# lyme_shield_system_gen2.net
KiCad netlist of a schematic drawn in EAGLE
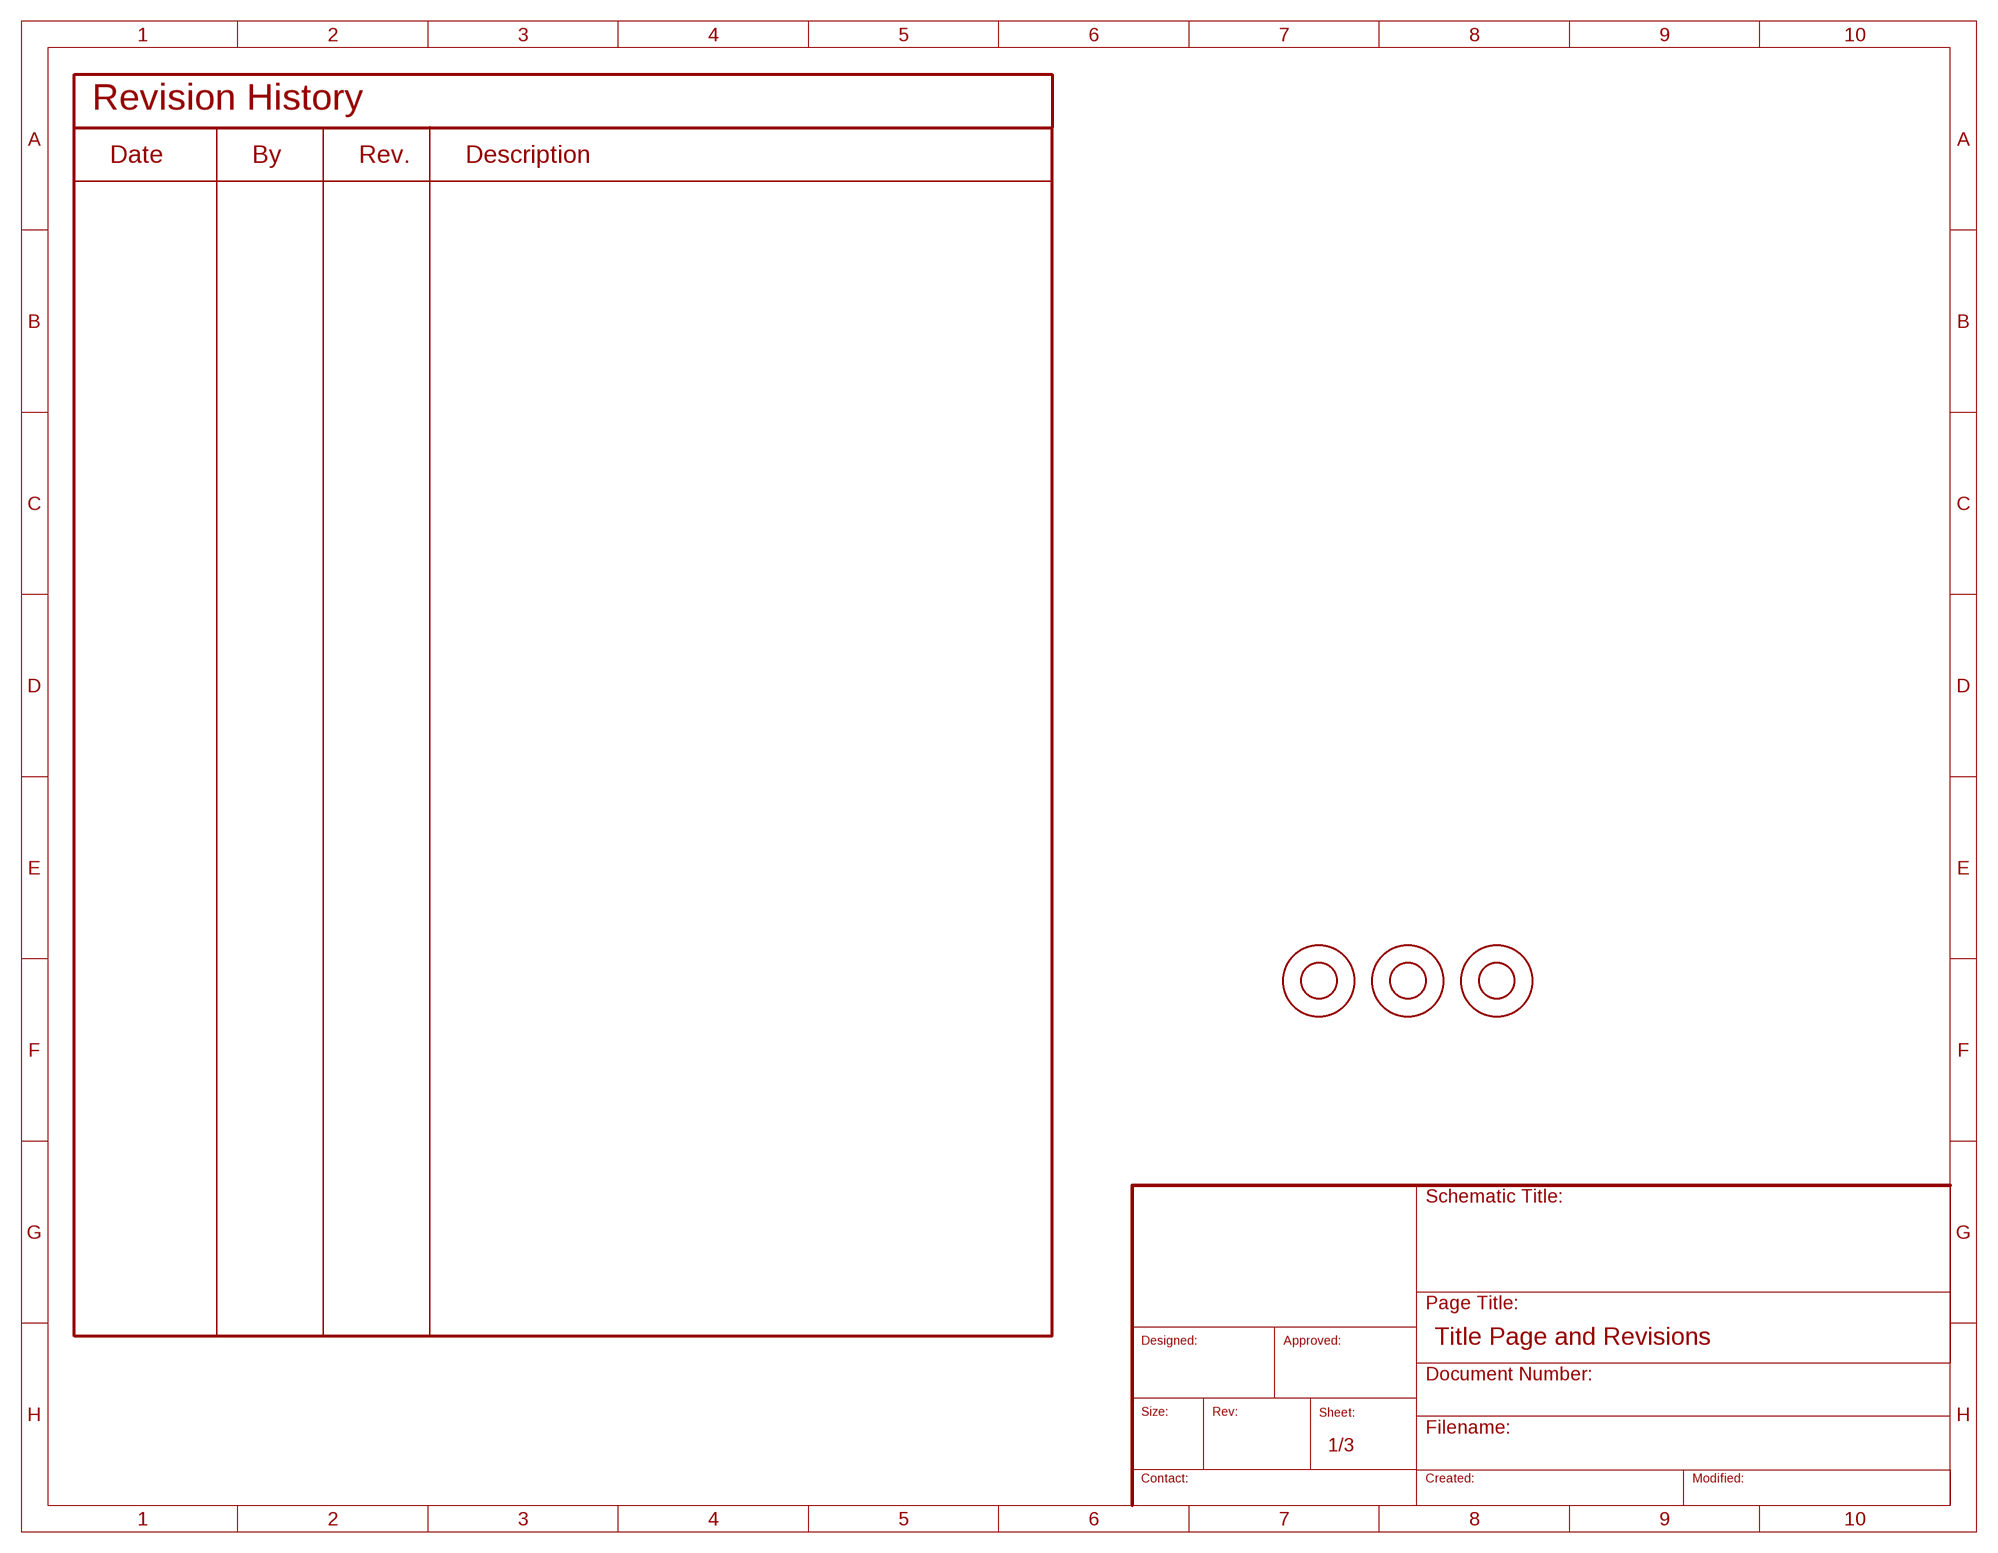
[diagram p0: schematic, sheet 1]
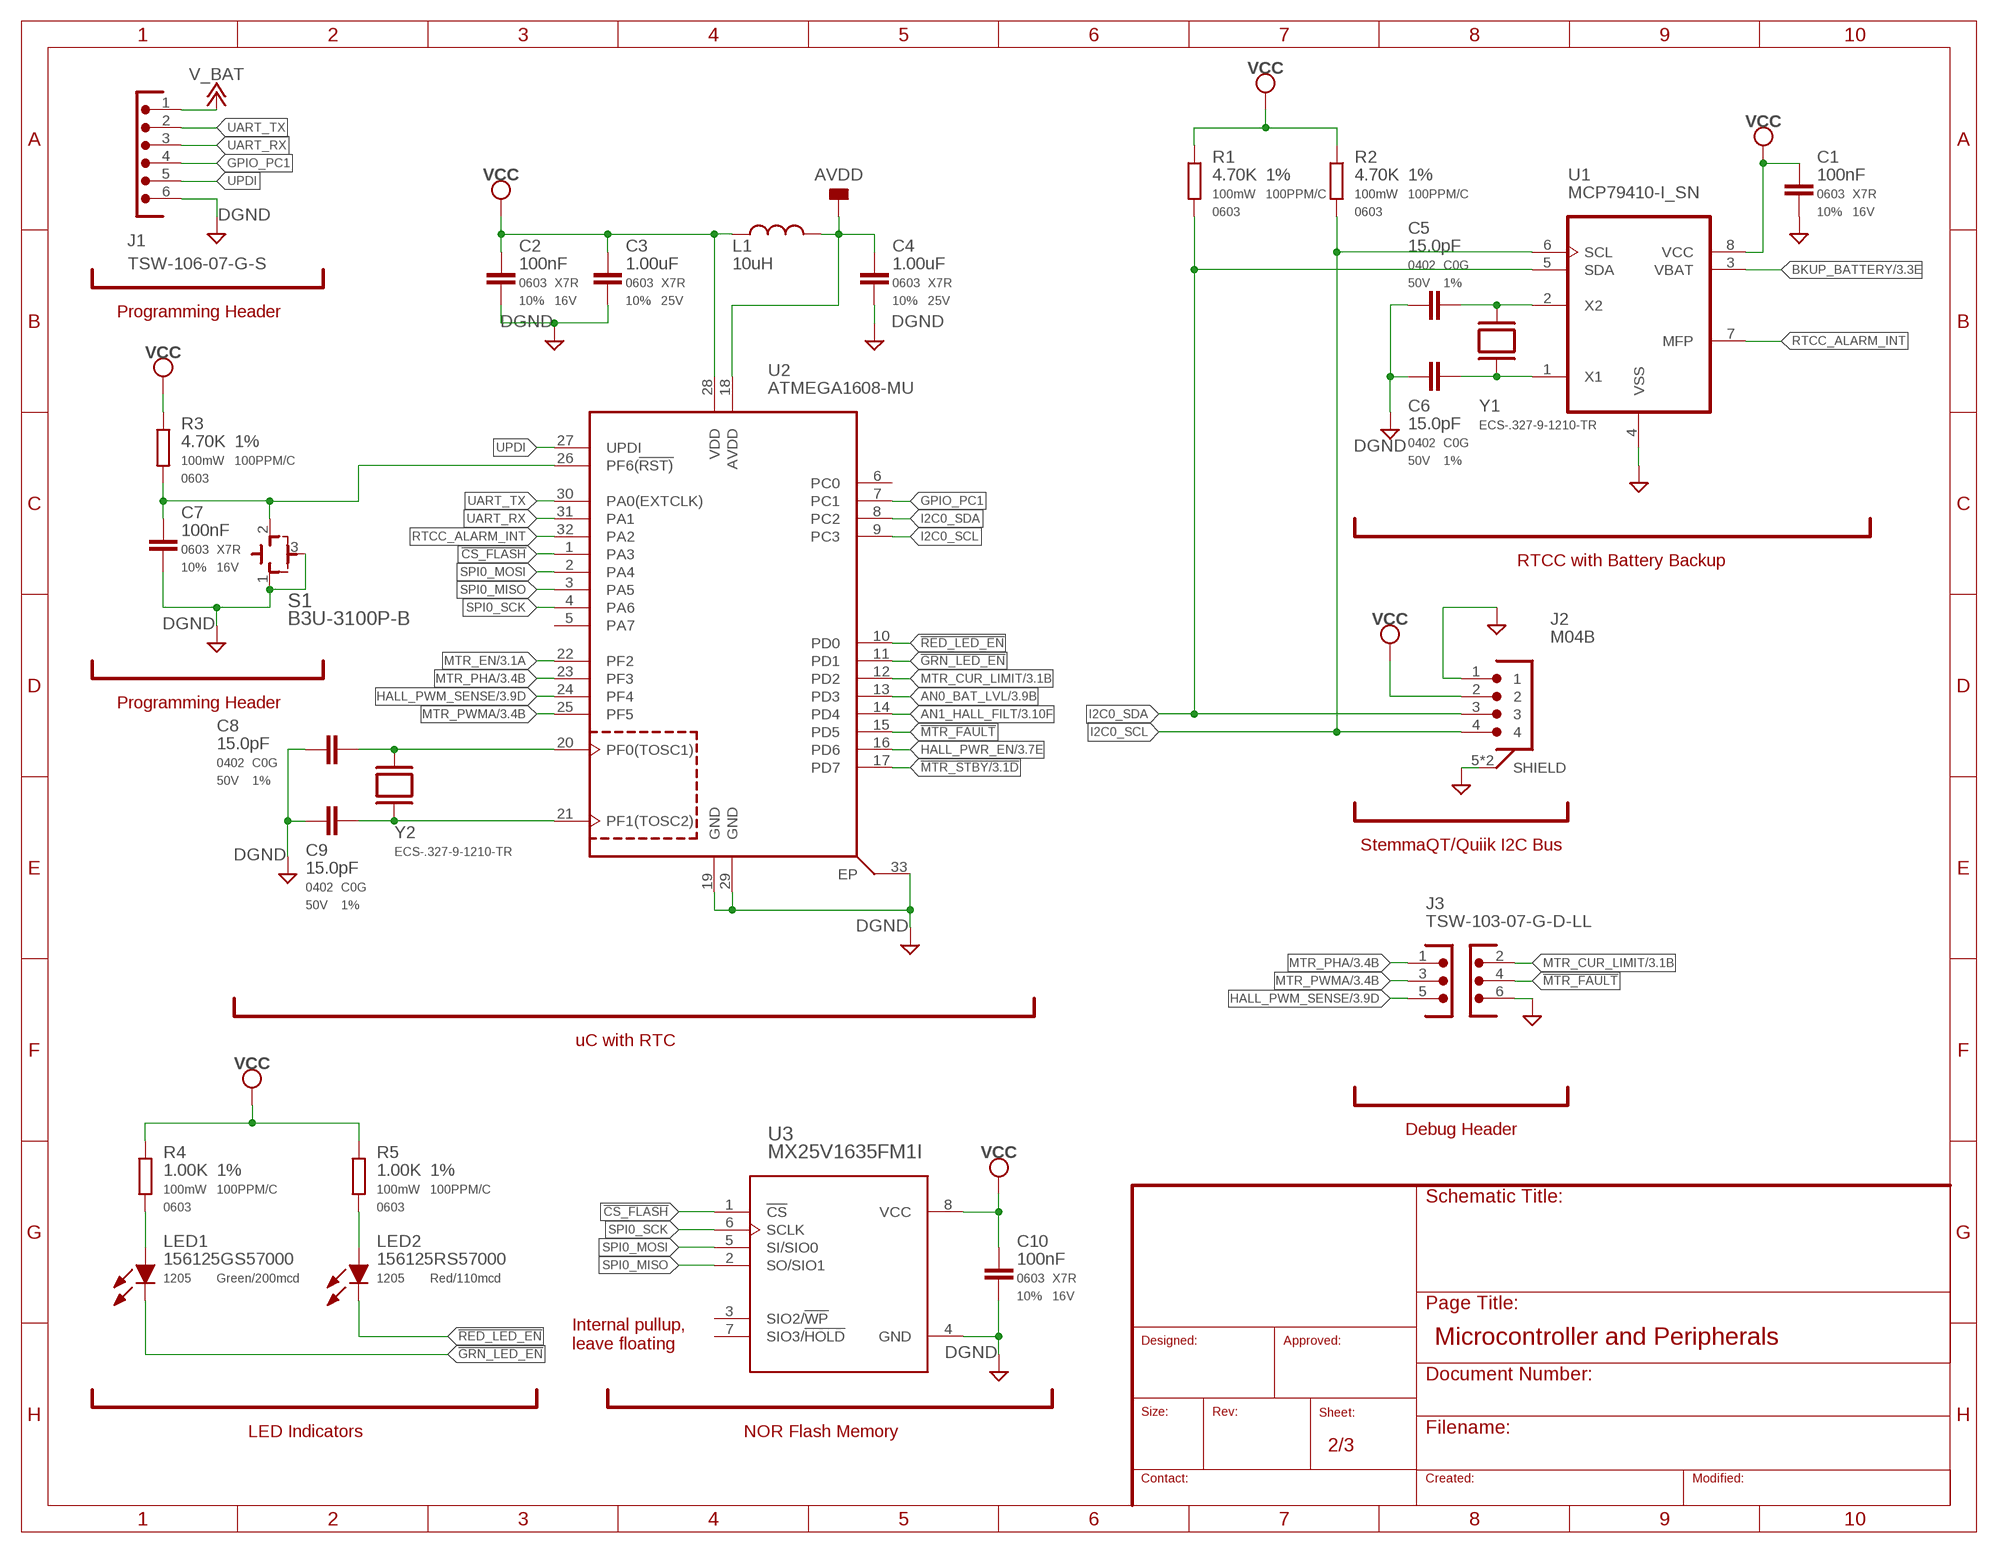
[diagram p1: schematic, sheet 2]
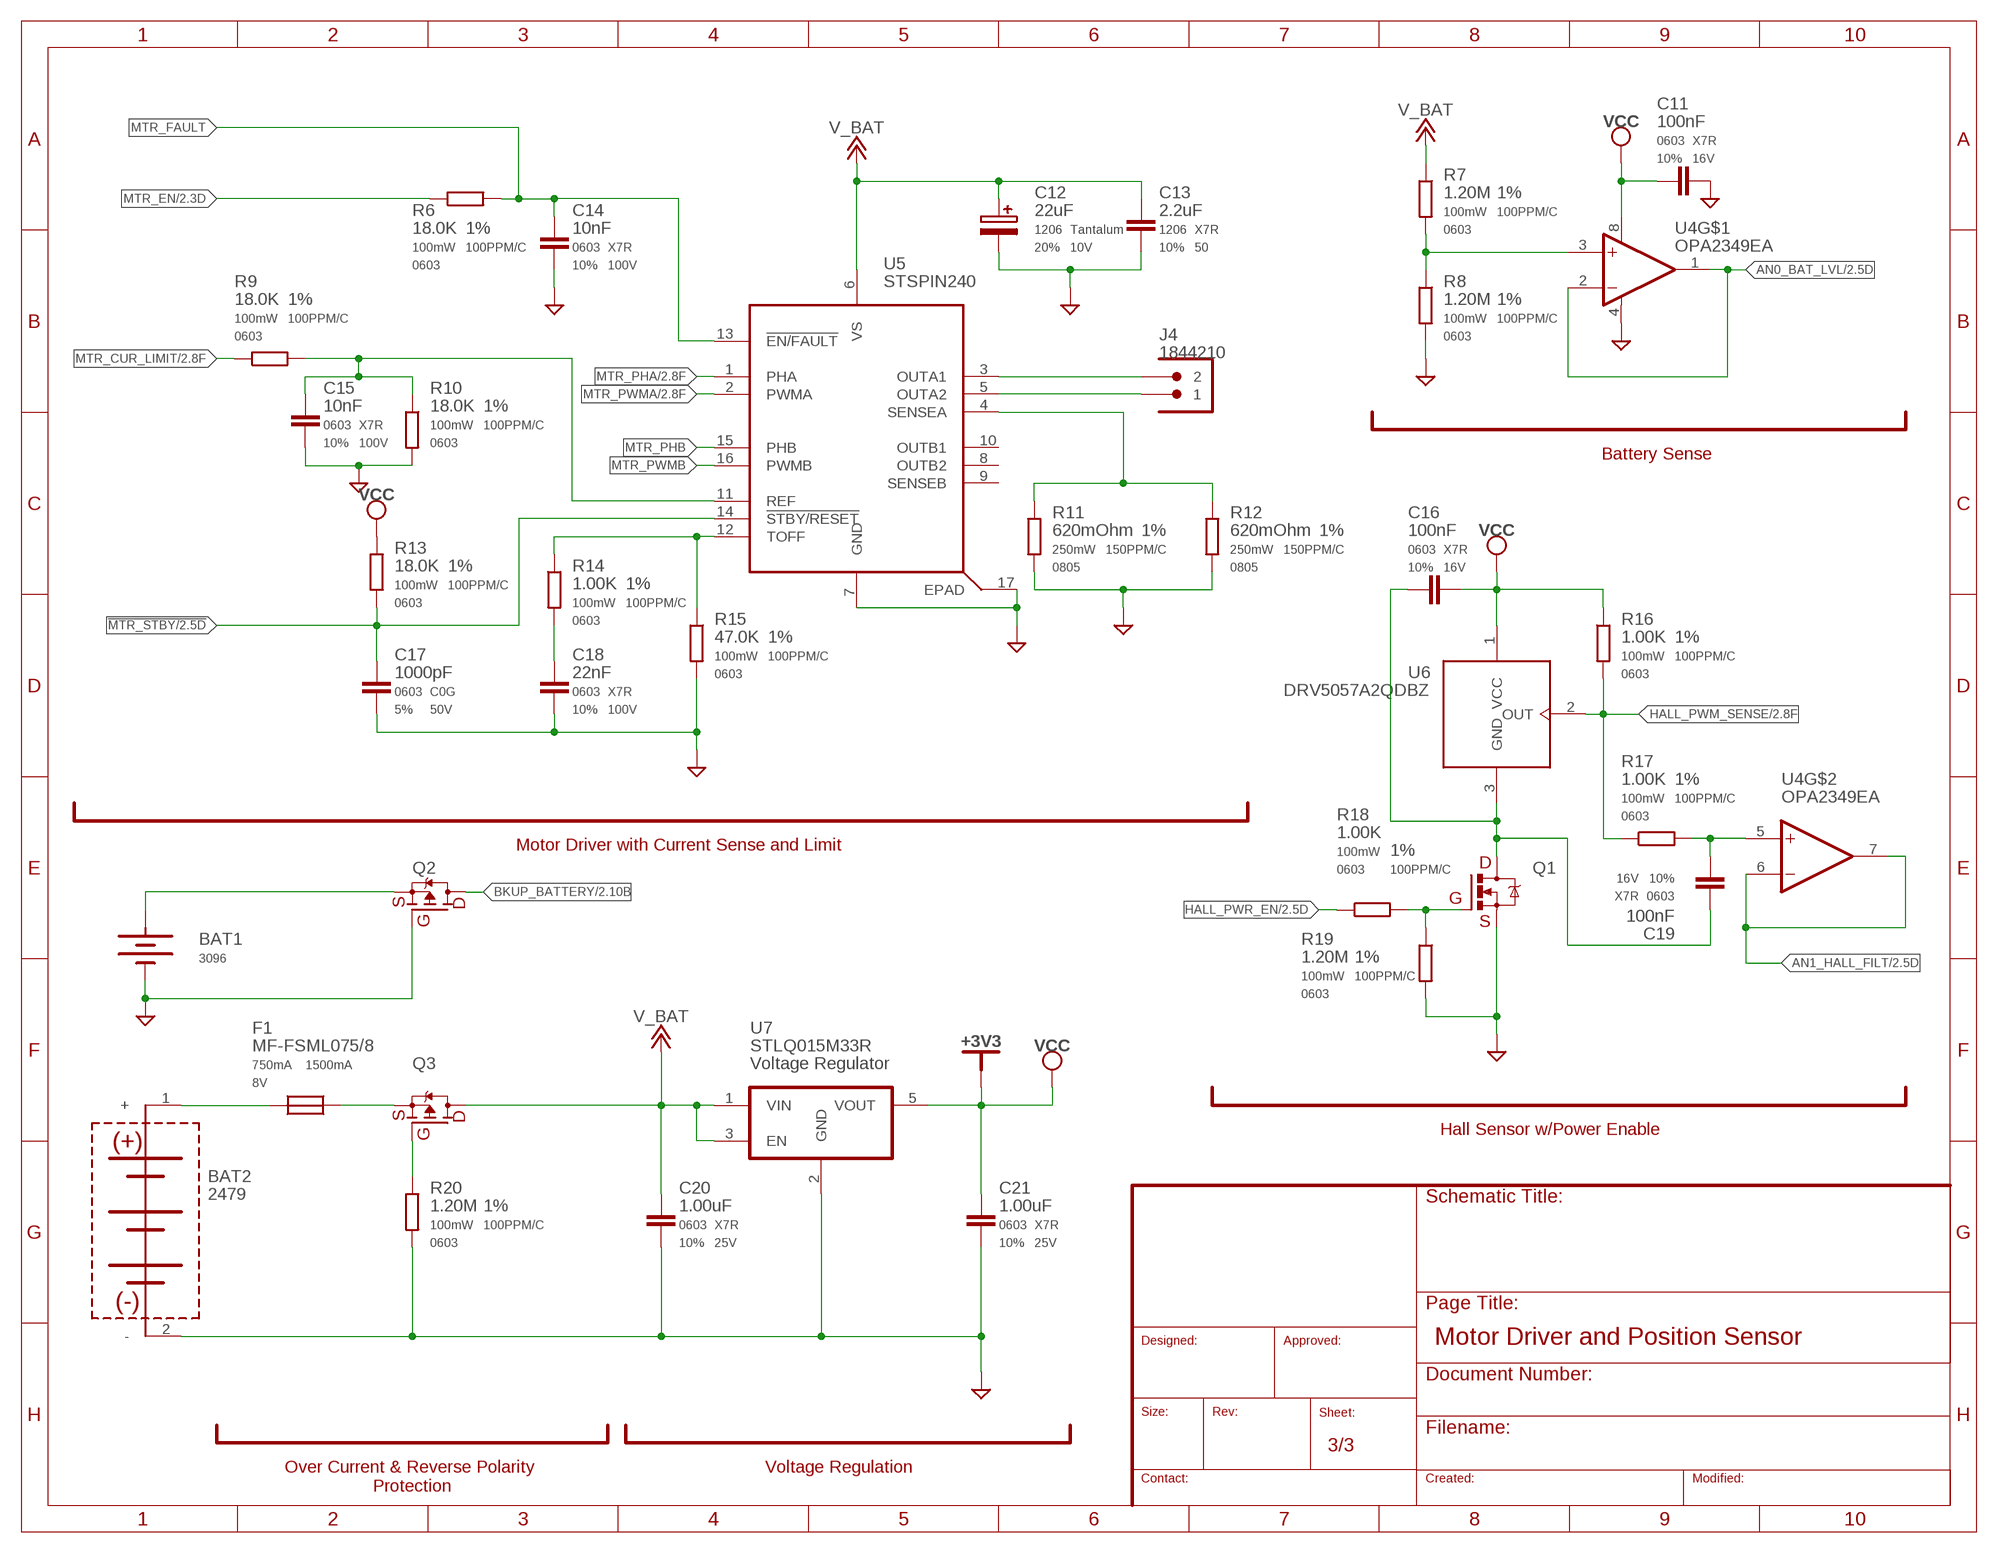
[diagram p2: schematic, sheet 3]

(export (version "E")
  (design (tool "Eeschema 10.0.6"))
  (components
    (comp (ref "BAT1")
      (value "3096")
      (footprint "eagle-import:3096")
      (fields (field (name "MOUSER_PART_NUMBER") "534-3096"))
      (libsource (lib "eagle-import") (part "3096"))
    )
    (comp (ref "BAT2")
      (value "2479")
      (footprint "eagle-import:2479")
      (fields (field (name "MOUSER_PART_NUMBER") "534-2479"))
      (libsource (lib "eagle-import") (part "2479"))
    )
    (comp (ref "C11")
      (value "100nF")
      (footprint "eagle-import:CAPC_0603_1608X90N")
      (fields
        (field (name "MANUFACTURER") "Murata")
        (field (name "PACKAGE") "0603")
        (field (name "TOL") "10%")
        (field (name "TYPE") "X7R")
        (field (name "VDC") "16V")
      )
      (libsource (lib "eagle-import") (part "GCM?188R71C104KA37J"))
    )
    (comp (ref "C12")
      (value "22uF")
      (footprint "eagle-import:CAPC_1206")
      (fields
        (field (name "MANUFACTURER") "AVX")
        (field (name "PACKAGE") "1206")
        (field (name "TOL") "20%")
        (field (name "TYPE") "Tantalum")
        (field (name "VDC") "10V")
      )
      (libsource (lib "eagle-import") (part "TAJ?C226M010RNJ"))
    )
    (comp (ref "C13")
      (value "2.2uF")
      (footprint "eagle-import:CAPC_1206")
      (fields
        (field (name "MANUFACTURER") "Murata")
        (field (name "PACKAGE") "1206")
        (field (name "TOL") "10%")
        (field (name "TYPE") "X7R")
        (field (name "VDC") "50")
      )
      (libsource (lib "eagle-import") (part "GCM?31CR71H225KA55L"))
    )
    (comp (ref "C14")
      (value "10nF")
      (footprint "eagle-import:CAPC_0603_1608X90N")
      (fields
        (field (name "MANUFACTURER") "Murata")
        (field (name "PACKAGE") "0603")
        (field (name "TOL") "10%")
        (field (name "TYPE") "X7R")
        (field (name "VDC") "100V")
      )
      (libsource (lib "eagle-import") (part "GCM?188R72A103KA37D"))
    )
    (comp (ref "C15")
      (value "10nF")
      (footprint "eagle-import:CAPC_0603_1608X90N")
      (fields
        (field (name "MANUFACTURER") "Murata")
        (field (name "PACKAGE") "0603")
        (field (name "TOL") "10%")
        (field (name "TYPE") "X7R")
        (field (name "VDC") "100V")
      )
      (libsource (lib "eagle-import") (part "GCM?188R72A103KA37D"))
    )
    (comp (ref "C16")
      (value "100nF")
      (footprint "eagle-import:CAPC_0603_1608X90N")
      (fields
        (field (name "MANUFACTURER") "Murata")
        (field (name "PACKAGE") "0603")
        (field (name "TOL") "10%")
        (field (name "TYPE") "X7R")
        (field (name "VDC") "16V")
      )
      (libsource (lib "eagle-import") (part "GCM?188R71C104KA37J"))
    )
    (comp (ref "C17")
      (value "1000pF")
      (footprint "eagle-import:CAPC_0603_1608X90N")
      (fields
        (field (name "MANUFACTURER") "Murata")
        (field (name "PACKAGE") "0603")
        (field (name "TOL") "5%")
        (field (name "TYPE") "C0G")
        (field (name "VDC") "50V")
      )
      (libsource (lib "eagle-import") (part "GCM?1885C1H102JA16J"))
    )
    (comp (ref "C18")
      (value "22nF")
      (footprint "eagle-import:CAPC_0603_1608X90N")
      (fields
        (field (name "MANUFACTURER") "Murata")
        (field (name "PACKAGE") "0603")
        (field (name "TOL") "10%")
        (field (name "TYPE") "X7R")
        (field (name "VDC") "100V")
      )
      (libsource (lib "eagle-import") (part "GCM?188R72A223KA37D"))
    )
    (comp (ref "C19")
      (value "100nF")
      (footprint "eagle-import:CAPC_0603_1608X90N")
      (fields
        (field (name "MANUFACTURER") "Murata")
        (field (name "PACKAGE") "0603")
        (field (name "TOL") "10%")
        (field (name "TYPE") "X7R")
        (field (name "VDC") "16V")
      )
      (libsource (lib "eagle-import") (part "GCM?188R71C104KA37J"))
    )
    (comp (ref "C20")
      (value "1.00uF")
      (footprint "eagle-import:CAPC_0603_1608X90N")
      (fields
        (field (name "MANUFACTURER") "Murata")
        (field (name "PACKAGE") "0603")
        (field (name "TOL") "10%")
        (field (name "TYPE") "X7R")
        (field (name "VDC") "25V")
      )
      (libsource (lib "eagle-import") (part "GCM?188R71E105KA64D"))
    )
    (comp (ref "C21")
      (value "1.00uF")
      (footprint "eagle-import:CAPC_0603_1608X90N")
      (fields
        (field (name "MANUFACTURER") "Murata")
        (field (name "PACKAGE") "0603")
        (field (name "TOL") "10%")
        (field (name "TYPE") "X7R")
        (field (name "VDC") "25V")
      )
      (libsource (lib "eagle-import") (part "GCM?188R71E105KA64D"))
    )
    (comp (ref "F1")
      (value "MF-FSML075/8")
      (footprint "eagle-import:FUSC1608X70N")
      (fields (field (name "IHOLD") "750mA") (field (name "ITRIP") "1500mA") (field (name "VMAX") "8V"))
      (libsource (lib "eagle-import") (part "MF-FSML?075/8"))
    )
    (comp (ref "J4")
      (value "1844210")
      (footprint "eagle-import:1844210-2-3.50")
      (libsource (lib "eagle-import") (part "1844210"))
    )
    (comp (ref "Q1")
      (value "FDN5632N-F085-FDN5632N_F085")
      (footprint "eagle-import:SOT-23")
      (fields (field (name "MANUFACTURER") "ON Semiconductor"))
      (libsource (lib "eagle-import") (part "FDN5632N-F085-FDN5632N_F085"))
    )
    (comp (ref "Q2")
      (value "PMOS_DMP2035U-7")
      (footprint "eagle-import:SOT-23")
      (fields (field (name "MF") "Diodes Incorporated") (field (name "MP") "DMP2035U-7"))
      (libsource (lib "eagle-import") (part "PMOS_DMP2035U-7"))
    )
    (comp (ref "Q3")
      (value "PMOS_DMP2035U-7")
      (footprint "eagle-import:SOT-23")
      (fields (field (name "MF") "Diodes Incorporated") (field (name "MP") "DMP2035U-7"))
      (libsource (lib "eagle-import") (part "PMOS_DMP2035U-7"))
    )
    (comp (ref "R6")
      (value "18.0K")
      (footprint "eagle-import:R0603K")
      (fields
        (field (name "MF") "Vishay")
        (field (name "PACKAGE") "0603")
        (field (name "PWR_RATE") "100mW")
        (field (name "TEMPCO") "100PPM/C")
        (field (name "TOLERANCE") "1%")
      )
      (libsource (lib "eagle-import") (part "CRCW?060318K0FKEAC"))
    )
    (comp (ref "R7")
      (value "1.20M")
      (footprint "eagle-import:R0603K")
      (fields
        (field (name "MF") "Vishay")
        (field (name "PACKAGE") "0603")
        (field (name "PWR_RATE") "100mW")
        (field (name "TEMPCO") "100PPM/C")
        (field (name "TOLERANCE") "1%")
      )
      (libsource (lib "eagle-import") (part "CRCW?06031M20FKEA"))
    )
    (comp (ref "R8")
      (value "1.20M")
      (footprint "eagle-import:R0603K")
      (fields
        (field (name "MF") "Vishay")
        (field (name "PACKAGE") "0603")
        (field (name "PWR_RATE") "100mW")
        (field (name "TEMPCO") "100PPM/C")
        (field (name "TOLERANCE") "1%")
      )
      (libsource (lib "eagle-import") (part "CRCW?06031M20FKEA"))
    )
    (comp (ref "R9")
      (value "18.0K")
      (footprint "eagle-import:R0603K")
      (fields
        (field (name "MF") "Vishay")
        (field (name "PACKAGE") "0603")
        (field (name "PWR_RATE") "100mW")
        (field (name "TEMPCO") "100PPM/C")
        (field (name "TOLERANCE") "1%")
      )
      (libsource (lib "eagle-import") (part "CRCW?060318K0FKEAC"))
    )
    (comp (ref "R10")
      (value "18.0K")
      (footprint "eagle-import:R0603K")
      (fields
        (field (name "MF") "Vishay")
        (field (name "PACKAGE") "0603")
        (field (name "PWR_RATE") "100mW")
        (field (name "TEMPCO") "100PPM/C")
        (field (name "TOLERANCE") "1%")
      )
      (libsource (lib "eagle-import") (part "CRCW?060318K0FKEAC"))
    )
    (comp (ref "R11")
      (value "620mOhm")
      (footprint "eagle-import:R0805K")
      (fields
        (field (name "MANUFACTURER") "Panasonic")
        (field (name "PACKAGE") "0805")
        (field (name "PWR_RATE") "250mW")
        (field (name "TEMPCO") "150PPM/C")
        (field (name "TOLERANCE") "1%")
      )
      (libsource (lib "eagle-import") (part "ERJ?U6QFR62V"))
    )
    (comp (ref "R12")
      (value "620mOhm")
      (footprint "eagle-import:R0805K")
      (fields
        (field (name "MANUFACTURER") "Panasonic")
        (field (name "PACKAGE") "0805")
        (field (name "PWR_RATE") "250mW")
        (field (name "TEMPCO") "150PPM/C")
        (field (name "TOLERANCE") "1%")
      )
      (libsource (lib "eagle-import") (part "ERJ?U6QFR62V"))
    )
    (comp (ref "R13")
      (value "18.0K")
      (footprint "eagle-import:R0603K")
      (fields
        (field (name "MF") "Vishay")
        (field (name "PACKAGE") "0603")
        (field (name "PWR_RATE") "100mW")
        (field (name "TEMPCO") "100PPM/C")
        (field (name "TOLERANCE") "1%")
      )
      (libsource (lib "eagle-import") (part "CRCW?060318K0FKEAC"))
    )
    (comp (ref "R14")
      (value "1.00K")
      (footprint "eagle-import:R0603K")
      (fields
        (field (name "MF") "Vishay")
        (field (name "PACKAGE") "0603")
        (field (name "PWR_RATE") "100mW")
        (field (name "TEMPCO") "100PPM/C")
        (field (name "TOLERANCE") "1%")
      )
      (libsource (lib "eagle-import") (part "CRCW?06031K00FKEAC"))
    )
    (comp (ref "R15")
      (value "47.0K")
      (footprint "eagle-import:R0603K")
      (fields
        (field (name "MF") "Vishay")
        (field (name "PACKAGE") "0603")
        (field (name "PWR_RATE") "100mW")
        (field (name "TEMPCO") "100PPM/C")
        (field (name "TOLERANCE") "1%")
      )
      (libsource (lib "eagle-import") (part "CRCW?060347K0FKEAC"))
    )
    (comp (ref "R16")
      (value "1.00K")
      (footprint "eagle-import:R0603K")
      (fields
        (field (name "MF") "Vishay")
        (field (name "PACKAGE") "0603")
        (field (name "PWR_RATE") "100mW")
        (field (name "TEMPCO") "100PPM/C")
        (field (name "TOLERANCE") "1%")
      )
      (libsource (lib "eagle-import") (part "CRCW?06031K00FKEAC"))
    )
    (comp (ref "R17")
      (value "1.00K")
      (footprint "eagle-import:R0603K")
      (fields
        (field (name "MF") "Vishay")
        (field (name "PACKAGE") "0603")
        (field (name "PWR_RATE") "100mW")
        (field (name "TEMPCO") "100PPM/C")
        (field (name "TOLERANCE") "1%")
      )
      (libsource (lib "eagle-import") (part "CRCW?06031K00FKEAC"))
    )
    (comp (ref "R18")
      (value "1.00K")
      (footprint "eagle-import:R0603K")
      (fields
        (field (name "MF") "Vishay")
        (field (name "PACKAGE") "0603")
        (field (name "PWR_RATE") "100mW")
        (field (name "TEMPCO") "100PPM/C")
        (field (name "TOLERANCE") "1%")
      )
      (libsource (lib "eagle-import") (part "CRCW?06031K00FKEAC"))
    )
    (comp (ref "R19")
      (value "1.20M")
      (footprint "eagle-import:R0603K")
      (fields
        (field (name "MF") "Vishay")
        (field (name "PACKAGE") "0603")
        (field (name "PWR_RATE") "100mW")
        (field (name "TEMPCO") "100PPM/C")
        (field (name "TOLERANCE") "1%")
      )
      (libsource (lib "eagle-import") (part "CRCW?06031M20FKEA"))
    )
    (comp (ref "R20")
      (value "1.20M")
      (footprint "eagle-import:R0603K")
      (fields
        (field (name "MF") "Vishay")
        (field (name "PACKAGE") "0603")
        (field (name "PWR_RATE") "100mW")
        (field (name "TEMPCO") "100PPM/C")
        (field (name "TOLERANCE") "1%")
      )
      (libsource (lib "eagle-import") (part "CRCW?06031M20FKEA"))
    )
    (comp (ref "U4")
      (value "OPA2349EA")
      (footprint "eagle-import:SOT65P280X145-8N")
      (fields
        (field (name "ARROW_PART_NUMBER") "OPA2349EA/3K")
        (field (name "MOUSER_PART_NUMBER") "595-OPA2349EA/3K")
      )
      (libsource (lib "eagle-import") (part "OPA2349EA"))
    )
    (comp (ref "U5")
      (value "STSPIN240")
      (footprint "eagle-import:VFQFPN(3X3X1.0MM-16L)")
      (fields (field (name "MOUSER_PART_NUMBER") "511-STSPIN240"))
      (libsource (lib "eagle-import") (part "STSPIN240"))
    )
    (comp (ref "U6")
      (value "DRV5057A2QDBZ")
      (footprint "eagle-import:SOT95P237X112-3N")
      (libsource (lib "eagle-import") (part "DRV5057QDBZA2"))
    )
    (comp (ref "U7")
      (value "STLQ015M33R")
      (footprint "eagle-import:SOT23-5L")
      (fields
        (field (name "DESC") "Voltage Regulator")
        (field (name "MF") "STM")
        (field (name "VOLTAGE") "3.3V")
      )
      (libsource (lib "eagle-import") (part "STLQ015MR33"))
    )
    (comp (ref "C1")
      (value "100nF")
      (footprint "eagle-import:CAPC_0603_1608X90N")
      (fields
        (field (name "MANUFACTURER") "Murata")
        (field (name "PACKAGE") "0603")
        (field (name "TOL") "10%")
        (field (name "TYPE") "X7R")
        (field (name "VDC") "16V")
      )
      (libsource (lib "eagle-import") (part "GCM?188R71C104KA37J"))
    )
    (comp (ref "C2")
      (value "100nF")
      (footprint "eagle-import:CAPC_0603_1608X90N")
      (fields
        (field (name "MANUFACTURER") "Murata")
        (field (name "PACKAGE") "0603")
        (field (name "TOL") "10%")
        (field (name "TYPE") "X7R")
        (field (name "VDC") "16V")
      )
      (libsource (lib "eagle-import") (part "GCM?188R71C104KA37J"))
    )
    (comp (ref "C3")
      (value "1.00uF")
      (footprint "eagle-import:CAPC_0603_1608X90N")
      (fields
        (field (name "MANUFACTURER") "Murata")
        (field (name "PACKAGE") "0603")
        (field (name "TOL") "10%")
        (field (name "TYPE") "X7R")
        (field (name "VDC") "25V")
      )
      (libsource (lib "eagle-import") (part "GCM?188R71E105KA64D"))
    )
    (comp (ref "C4")
      (value "1.00uF")
      (footprint "eagle-import:CAPC_0603_1608X90N")
      (fields
        (field (name "MANUFACTURER") "Murata")
        (field (name "PACKAGE") "0603")
        (field (name "TOL") "10%")
        (field (name "TYPE") "X7R")
        (field (name "VDC") "25V")
      )
      (libsource (lib "eagle-import") (part "GCM?188R71E105KA64D"))
    )
    (comp (ref "C5")
      (value "15.0pF")
      (footprint "eagle-import:CAPC_0402_1005X55N")
      (fields
        (field (name "MANUFACTURER") "Murata")
        (field (name "PACKAGE") "0402")
        (field (name "TOL") "1%")
        (field (name "TYPE") "C0G")
        (field (name "VDC") "50V")
      )
      (libsource (lib "eagle-import") (part "GCM?1555C1H150FA16D"))
    )
    (comp (ref "C6")
      (value "15.0pF")
      (footprint "eagle-import:CAPC_0402_1005X55N")
      (fields
        (field (name "MANUFACTURER") "Murata")
        (field (name "PACKAGE") "0402")
        (field (name "TOL") "1%")
        (field (name "TYPE") "C0G")
        (field (name "VDC") "50V")
      )
      (libsource (lib "eagle-import") (part "GCM?1555C1H150FA16D"))
    )
    (comp (ref "C7")
      (value "100nF")
      (footprint "eagle-import:CAPC_0603_1608X90N")
      (fields
        (field (name "MANUFACTURER") "Murata")
        (field (name "PACKAGE") "0603")
        (field (name "TOL") "10%")
        (field (name "TYPE") "X7R")
        (field (name "VDC") "16V")
      )
      (libsource (lib "eagle-import") (part "GCM?188R71C104KA37J"))
    )
    (comp (ref "C8")
      (value "15.0pF")
      (footprint "eagle-import:CAPC_0402_1005X55N")
      (fields
        (field (name "MANUFACTURER") "Murata")
        (field (name "PACKAGE") "0402")
        (field (name "TOL") "1%")
        (field (name "TYPE") "C0G")
        (field (name "VDC") "50V")
      )
      (libsource (lib "eagle-import") (part "GCM?1555C1H150FA16D"))
    )
    (comp (ref "C9")
      (value "15.0pF")
      (footprint "eagle-import:CAPC_0402_1005X55N")
      (fields
        (field (name "MANUFACTURER") "Murata")
        (field (name "PACKAGE") "0402")
        (field (name "TOL") "1%")
        (field (name "TYPE") "C0G")
        (field (name "VDC") "50V")
      )
      (libsource (lib "eagle-import") (part "GCM?1555C1H150FA16D"))
    )
    (comp (ref "C10")
      (value "100nF")
      (footprint "eagle-import:CAPC_0603_1608X90N")
      (fields
        (field (name "MANUFACTURER") "Murata")
        (field (name "PACKAGE") "0603")
        (field (name "TOL") "10%")
        (field (name "TYPE") "X7R")
        (field (name "VDC") "16V")
      )
      (libsource (lib "eagle-import") (part "GCM?188R71C104KA37J"))
    )
    (comp (ref "J1")
      (value "TSW-106-07-G-S")
      (footprint "eagle-import:HDR-100MIL-1X6-THRU")
      (libsource (lib "eagle-import") (part "TSW-106-07-G-S"))
    )
    (comp (ref "J2")
      (value "M04B")
      (footprint "eagle-import:SM04B-SRSS-TB(LFSN)")
      (fields (field (name "MANUFACTURER_PART_NUMBER") "SM04B-SRSS-TB(LFSN)"))
      (libsource (lib "eagle-import") (part "?M04B"))
    )
    (comp (ref "J3")
      (value "TSW-103-07-G-D-LL")
      (footprint "eagle-import:HDRV6W64P254_2X3_762X495X838P")
      (fields (field (name "MOUSER_PART_NUMBER") "200-TSW10307GDLL"))
      (libsource (lib "eagle-import") (part "TSW-103-07-G-D-LL"))
    )
    (comp (ref "L1")
      (value "10uH")
      (footprint "eagle-import:INDC1608X90N")
      (fields (field (name "MF") "Taiyo Yuden") (field (name "MP") "LB1608T100M"))
      (libsource (lib "eagle-import") (part "LB1608T100M"))
    )
    (comp (ref "LED1")
      (value "156125GS57000")
      (footprint "eagle-import:LEDC3212X120N")
      (fields (field (name "PACKAGE") "1205"))
      (libsource (lib "eagle-import") (part "15612557000GS"))
    )
    (comp (ref "LED2")
      (value "156125RS57000")
      (footprint "eagle-import:LEDC3212X120N")
      (fields (field (name "PACKAGE") "1205"))
      (libsource (lib "eagle-import") (part "15612557000RS"))
    )
    (comp (ref "R1")
      (value "4.70K")
      (footprint "eagle-import:R0603K")
      (fields
        (field (name "MF") "Vishay")
        (field (name "PACKAGE") "0603")
        (field (name "PWR_RATE") "100mW")
        (field (name "TEMPCO") "100PPM/C")
        (field (name "TOLERANCE") "1%")
      )
      (libsource (lib "eagle-import") (part "CRCW?06034K70FKEA"))
    )
    (comp (ref "R2")
      (value "4.70K")
      (footprint "eagle-import:R0603K")
      (fields
        (field (name "MF") "Vishay")
        (field (name "PACKAGE") "0603")
        (field (name "PWR_RATE") "100mW")
        (field (name "TEMPCO") "100PPM/C")
        (field (name "TOLERANCE") "1%")
      )
      (libsource (lib "eagle-import") (part "CRCW?06034K70FKEA"))
    )
    (comp (ref "R3")
      (value "4.70K")
      (footprint "eagle-import:R0603K")
      (fields
        (field (name "MF") "Vishay")
        (field (name "PACKAGE") "0603")
        (field (name "PWR_RATE") "100mW")
        (field (name "TEMPCO") "100PPM/C")
        (field (name "TOLERANCE") "1%")
      )
      (libsource (lib "eagle-import") (part "CRCW?06034K70FKEA"))
    )
    (comp (ref "R4")
      (value "1.00K")
      (footprint "eagle-import:R0603K")
      (fields
        (field (name "MF") "Vishay")
        (field (name "PACKAGE") "0603")
        (field (name "PWR_RATE") "100mW")
        (field (name "TEMPCO") "100PPM/C")
        (field (name "TOLERANCE") "1%")
      )
      (libsource (lib "eagle-import") (part "CRCW?06031K00FKEAC"))
    )
    (comp (ref "R5")
      (value "1.00K")
      (footprint "eagle-import:R0603K")
      (fields
        (field (name "MF") "Vishay")
        (field (name "PACKAGE") "0603")
        (field (name "PWR_RATE") "100mW")
        (field (name "TEMPCO") "100PPM/C")
        (field (name "TOLERANCE") "1%")
      )
      (libsource (lib "eagle-import") (part "CRCW?06031K00FKEAC"))
    )
    (comp (ref "S1")
      (value "B3U-3100P-B")
      (footprint "eagle-import:B3U-3100P-B")
      (libsource (lib "eagle-import") (part "B3U-3100P-B"))
    )
    (comp (ref "U1")
      (value "MCP79410-I_SN")
      (footprint "eagle-import:SOIC127P600X175-8N")
      (fields
        (field (name "ARROW_PART_NUMBER") "MCP79410-I/SN")
        (field (name "MOUSER_PART_NUMBER") "579-MCP79410-I/SN")
      )
      (libsource (lib "eagle-import") (part "MCP79410-I_SN"))
    )
    (comp (ref "U2")
      (value "ATMEGA1608-MU")
      (footprint "eagle-import:QFN50P500X500X90-33N")
      (fields (field (name "MOUSER_PART_NUMBER") "556-ATMEGA1608-MU"))
      (libsource (lib "eagle-import") (part "ATMEGA1608-MU"))
    )
    (comp (ref "U3")
      (value "MX25V1635FM1I")
      (footprint "eagle-import:SOIC127P600X175-8N")
      (fields (field (name "MANUFACTURER") "Macronix"))
      (libsource (lib "eagle-import") (part "MX25V?M1I1635F"))
    )
    (comp (ref "Y1")
      (value "ECS-.327-9-1210-TR")
      (footprint "eagle-import:XTAL_ECS-.327-9-1210-TR")
      (fields (field (name "DIGI-KEY_PART_NUMBER") "XC2283CT-ND") (field (name "MF") "ECS Inc."))
      (libsource (lib "eagle-import") (part "ECS-.327-9-1210-TR"))
    )
    (comp (ref "Y2")
      (value "ECS-.327-9-1210-TR")
      (footprint "eagle-import:XTAL_ECS-.327-9-1210-TR")
      (fields (field (name "DIGI-KEY_PART_NUMBER") "XC2283CT-ND") (field (name "MF") "ECS Inc."))
      (libsource (lib "eagle-import") (part "ECS-.327-9-1210-TR"))
    )
    (comp (ref "FID1")
      (value "FIDUCIAL_1MM_TOP_BOTTOM")
      (footprint "eagle-import:FIDUCIAL_1MM_TOP_BOTTOM")
      (libsource (lib "eagle-import") (part "FIDUCIAL_1MM_TOP_BOTTOM"))
    )
    (comp (ref "FID2")
      (value "FIDUCIAL_1MM_TOP_BOTTOM")
      (footprint "eagle-import:FIDUCIAL_1MM_TOP_BOTTOM")
      (libsource (lib "eagle-import") (part "FIDUCIAL_1MM_TOP_BOTTOM"))
    )
    (comp (ref "FID3")
      (value "FIDUCIAL_1MM_TOP_BOTTOM")
      (footprint "eagle-import:FIDUCIAL_1MM_TOP_BOTTOM")
      (libsource (lib "eagle-import") (part "FIDUCIAL_1MM_TOP_BOTTOM"))
    )
  )
  (nets
    (net (code "1") (name "+3V3") (class "Default")
      (node (ref "C1") (pin "1") (pinfunction "1_1") (pintype "passive"))
      (node (ref "C10") (pin "1") (pinfunction "1_1") (pintype "passive"))
      (node (ref "C11") (pin "2") (pinfunction "2_2") (pintype "passive"))
      (node (ref "C16") (pin "1") (pinfunction "1_1") (pintype "passive"))
      (node (ref "C2") (pin "1") (pinfunction "1_1") (pintype "passive"))
      (node (ref "C21") (pin "1") (pinfunction "1_1") (pintype "passive"))
      (node (ref "C3") (pin "1") (pinfunction "1_1") (pintype "passive"))
      (node (ref "J2") (pin "2") (pinfunction "2_2") (pintype "bidirectional"))
      (node (ref "L1") (pin "1") (pinfunction "1_1") (pintype "passive"))
      (node (ref "R1") (pin "1") (pinfunction "1_1") (pintype "passive"))
      (node (ref "R13") (pin "1") (pinfunction "1_1") (pintype "passive"))
      (node (ref "R16") (pin "1") (pinfunction "1_1") (pintype "passive"))
      (node (ref "R2") (pin "1") (pinfunction "1_1") (pintype "passive"))
      (node (ref "R3") (pin "1") (pinfunction "1_1") (pintype "passive"))
      (node (ref "R4") (pin "1") (pinfunction "1_1") (pintype "passive"))
      (node (ref "R5") (pin "1") (pinfunction "1_1") (pintype "passive"))
      (node (ref "U1") (pin "8") (pinfunction "VCC_8") (pintype "bidirectional"))
      (node (ref "U2") (pin "28") (pinfunction "VDD_28") (pintype "bidirectional"))
      (node (ref "U3") (pin "8") (pinfunction "VCC_8") (pintype "power_in"))
      (node (ref "U4") (pin "8") (pinfunction "V+_8") (pintype "power_in"))
      (node (ref "U6") (pin "1") (pinfunction "VCC_1") (pintype "bidirectional"))
      (node (ref "U7") (pin "5") (pinfunction "VOUT_5") (pintype "power_in"))
    )
    (net (code "2") (name "AN0_BAT_LVL") (class "Default")
      (node (ref "U2") (pin "13") (pinfunction "PD3_13") (pintype "bidirectional"))
      (node (ref "U4") (pin "1") (pinfunction "OUT_1") (pintype "output"))
      (node (ref "U4") (pin "2") (pinfunction "-IN_2") (pintype "input"))
    )
    (net (code "3") (name "AN1_HALL_FILT") (class "Default")
      (node (ref "U2") (pin "14") (pinfunction "PD4_14") (pintype "bidirectional"))
      (node (ref "U4") (pin "6") (pinfunction "-IN_6") (pintype "input"))
      (node (ref "U4") (pin "7") (pinfunction "OUT_7") (pintype "output"))
    )
    (net (code "4") (name "AVDD") (class "Default")
      (node (ref "C4") (pin "1") (pinfunction "1_1") (pintype "passive"))
      (node (ref "L1") (pin "2") (pinfunction "2_2") (pintype "passive"))
      (node (ref "U2") (pin "18") (pinfunction "AVDD_18") (pintype "bidirectional"))
    )
    (net (code "5") (name "BKUP_BATTERY") (class "Default")
      (node (ref "Q2") (pin "1") (pinfunction "D_1") (pintype "passive"))
      (node (ref "U1") (pin "3") (pinfunction "VBAT_3") (pintype "bidirectional"))
    )
    (net (code "6") (name "DGND") (class "Default")
      (node (ref "BAT1") (pin "1") (pinfunction "-_1") (pintype "power_in"))
      (node (ref "BAT1") (pin "3") (pinfunction "-_3") (pintype "power_in"))
      (node (ref "BAT2") (pin "2") (pinfunction "-_2") (pintype "bidirectional"))
      (node (ref "C1") (pin "2") (pinfunction "2_2") (pintype "passive"))
      (node (ref "C10") (pin "2") (pinfunction "2_2") (pintype "passive"))
      (node (ref "C11") (pin "1") (pinfunction "1_1") (pintype "passive"))
      (node (ref "C12") (pin "2") (pinfunction "-_2") (pintype "bidirectional"))
      (node (ref "C13") (pin "2") (pinfunction "2_2") (pintype "passive"))
      (node (ref "C14") (pin "2") (pinfunction "2_2") (pintype "passive"))
      (node (ref "C15") (pin "2") (pinfunction "2_2") (pintype "passive"))
      (node (ref "C17") (pin "2") (pinfunction "2_2") (pintype "passive"))
      (node (ref "C18") (pin "2") (pinfunction "2_2") (pintype "passive"))
      (node (ref "C2") (pin "2") (pinfunction "2_2") (pintype "passive"))
      (node (ref "C20") (pin "2") (pinfunction "2_2") (pintype "passive"))
      (node (ref "C21") (pin "2") (pinfunction "2_2") (pintype "passive"))
      (node (ref "C3") (pin "2") (pinfunction "2_2") (pintype "passive"))
      (node (ref "C4") (pin "2") (pinfunction "2_2") (pintype "passive"))
      (node (ref "C5") (pin "2") (pinfunction "2_2") (pintype "passive"))
      (node (ref "C6") (pin "2") (pinfunction "2_2") (pintype "passive"))
      (node (ref "C7") (pin "2") (pinfunction "2_2") (pintype "passive"))
      (node (ref "C8") (pin "2") (pinfunction "2_2") (pintype "passive"))
      (node (ref "C9") (pin "2") (pinfunction "2_2") (pintype "passive"))
      (node (ref "J1") (pin "6") (pinfunction "6_6") (pintype "passive"))
      (node (ref "J2") (pin "1") (pinfunction "1_1") (pintype "bidirectional"))
      (node (ref "J2") (pin "5") (pinfunction "SHIELD_5") (pintype "bidirectional"))
      (node (ref "J2") (pin "6") (pinfunction "SHIELD_6") (pintype "bidirectional"))
      (node (ref "J3") (pin "6") (pinfunction "6_6") (pintype "passive"))
      (node (ref "Q1") (pin "2") (pinfunction "S_2") (pintype "passive"))
      (node (ref "Q2") (pin "3") (pinfunction "G_3") (pintype "passive"))
      (node (ref "R10") (pin "2") (pinfunction "2_2") (pintype "passive"))
      (node (ref "R11") (pin "2") (pinfunction "2_2") (pintype "passive"))
      (node (ref "R12") (pin "2") (pinfunction "2_2") (pintype "passive"))
      (node (ref "R15") (pin "2") (pinfunction "2_2") (pintype "passive"))
      (node (ref "R19") (pin "2") (pinfunction "2_2") (pintype "passive"))
      (node (ref "R20") (pin "2") (pinfunction "2_2") (pintype "passive"))
      (node (ref "R8") (pin "2") (pinfunction "2_2") (pintype "passive"))
      (node (ref "S1") (pin "1") (pinfunction "COM_1") (pintype "bidirectional"))
      (node (ref "S1") (pin "3") (pinfunction "COM1_3") (pintype "bidirectional"))
      (node (ref "U1") (pin "4") (pinfunction "VSS_4") (pintype "bidirectional"))
      (node (ref "U2") (pin "19") (pinfunction "GND_19") (pintype "bidirectional"))
      (node (ref "U2") (pin "29") (pinfunction "GND_29") (pintype "bidirectional"))
      (node (ref "U2") (pin "33") (pinfunction "EP_33") (pintype "bidirectional"))
      (node (ref "U3") (pin "4") (pinfunction "GND_4") (pintype "passive"))
      (node (ref "U4") (pin "4") (pinfunction "V-_4") (pintype "power_in"))
      (node (ref "U5") (pin "17") (pinfunction "EPAD_17") (pintype "bidirectional"))
      (node (ref "U5") (pin "7") (pinfunction "GND_7") (pintype "bidirectional"))
      (node (ref "U7") (pin "2") (pinfunction "GND_2") (pintype "power_in"))
    )
    (net (code "7") (name "GPIO_PC1") (class "Default")
      (node (ref "J1") (pin "4") (pinfunction "4_4") (pintype "passive"))
      (node (ref "U2") (pin "7") (pinfunction "PC1_7") (pintype "bidirectional"))
    )
    (net (code "8") (name "HALL_PWM_SENSE") (class "Default")
      (node (ref "J3") (pin "5") (pinfunction "5_5") (pintype "passive"))
      (node (ref "R16") (pin "2") (pinfunction "2_2") (pintype "passive"))
      (node (ref "R17") (pin "1") (pinfunction "1_1") (pintype "passive"))
      (node (ref "U2") (pin "24") (pinfunction "PF4_24") (pintype "bidirectional"))
      (node (ref "U6") (pin "2") (pinfunction "OUT_2") (pintype "bidirectional"))
    )
    (net (code "9") (name "HALL_PWR_EN") (class "Default")
      (node (ref "R18") (pin "1") (pinfunction "1_1") (pintype "passive"))
      (node (ref "U2") (pin "16") (pinfunction "PD6_16") (pintype "bidirectional"))
    )
    (net (code "10") (name "I2C0_SCL") (class "Default")
      (node (ref "J2") (pin "4") (pinfunction "4_4") (pintype "bidirectional"))
      (node (ref "R2") (pin "2") (pinfunction "2_2") (pintype "passive"))
      (node (ref "U1") (pin "6") (pinfunction "SCL_6") (pintype "input"))
      (node (ref "U2") (pin "9") (pinfunction "PC3_9") (pintype "bidirectional"))
    )
    (net (code "11") (name "I2C0_SDA") (class "Default")
      (node (ref "J2") (pin "3") (pinfunction "3_3") (pintype "bidirectional"))
      (node (ref "R1") (pin "2") (pinfunction "2_2") (pintype "passive"))
      (node (ref "U1") (pin "5") (pinfunction "SDA_5") (pintype "bidirectional"))
      (node (ref "U2") (pin "8") (pinfunction "PC2_8") (pintype "bidirectional"))
    )
    (net (code "12") (name "MTR_CUR_LIMIT") (class "Default")
      (node (ref "J3") (pin "2") (pinfunction "2_2") (pintype "passive"))
      (node (ref "R9") (pin "1") (pinfunction "1_1") (pintype "passive"))
      (node (ref "U2") (pin "12") (pinfunction "PD2_12") (pintype "bidirectional"))
    )
    (net (code "13") (name "MTR_EN") (class "Default")
      (node (ref "R6") (pin "1") (pinfunction "1_1") (pintype "passive"))
      (node (ref "U2") (pin "22") (pinfunction "PF2_22") (pintype "bidirectional"))
    )
    (net (code "14") (name "MTR_FAULT") (class "Default")
      (node (ref "C14") (pin "1") (pinfunction "1_1") (pintype "passive"))
      (node (ref "R6") (pin "2") (pinfunction "2_2") (pintype "passive"))
      (node (ref "U5") (pin "13") (pinfunction "~{EN/FAULT}_13") (pintype "bidirectional"))
    )
    (net (code "15") (name "MTR_PHA") (class "Default")
      (node (ref "J3") (pin "1") (pinfunction "1_1") (pintype "passive"))
      (node (ref "U2") (pin "23") (pinfunction "PF3_23") (pintype "bidirectional"))
      (node (ref "U5") (pin "1") (pinfunction "PHA_1") (pintype "bidirectional"))
    )
    (net (code "16") (name "MTR_PHB") (class "Default")
      (node (ref "U5") (pin "15") (pinfunction "PHB_15") (pintype "bidirectional"))
    )
    (net (code "17") (name "MTR_PWMA") (class "Default")
      (node (ref "J3") (pin "3") (pinfunction "3_3") (pintype "passive"))
      (node (ref "U2") (pin "25") (pinfunction "PF5_25") (pintype "bidirectional"))
      (node (ref "U5") (pin "2") (pinfunction "PWMA_2") (pintype "bidirectional"))
    )
    (net (code "18") (name "MTR_PWMB") (class "Default")
      (node (ref "U5") (pin "16") (pinfunction "PWMB_16") (pintype "bidirectional"))
    )
    (net (code "19") (name "Net-(BAT1-+)") (class "Default")
      (node (ref "BAT1") (pin "2") (pinfunction "+_2") (pintype "power_in"))
      (node (ref "Q2") (pin "2") (pinfunction "S_2") (pintype "passive"))
    )
    (net (code "20") (name "Net-(BAT2-+)") (class "Default")
      (node (ref "BAT2") (pin "1") (pinfunction "+_1") (pintype "bidirectional"))
      (node (ref "F1") (pin "1") (pinfunction "1_1") (pintype "bidirectional"))
    )
    (net (code "21") (name "Net-(C18-Pad1)") (class "Default")
      (node (ref "C18") (pin "1") (pinfunction "1_1") (pintype "passive"))
      (node (ref "R14") (pin "2") (pinfunction "2_2") (pintype "passive"))
    )
    (net (code "22") (name "Net-(J4-1)") (class "Default")
      (node (ref "J4") (pin "P$1") (pinfunction "1_P$1") (pintype "bidirectional"))
      (node (ref "U5") (pin "5") (pinfunction "OUTA2_5") (pintype "bidirectional"))
    )
    (net (code "23") (name "Net-(J4-2)") (class "Default")
      (node (ref "J4") (pin "P$2") (pinfunction "2_P$2") (pintype "bidirectional"))
      (node (ref "U5") (pin "3") (pinfunction "OUTA1_3") (pintype "bidirectional"))
    )
    (net (code "24") (name "Net-(LED1-A)") (class "Default")
      (node (ref "LED1") (pin "2") (pinfunction "A_2") (pintype "bidirectional"))
      (node (ref "R4") (pin "2") (pinfunction "2_2") (pintype "passive"))
    )
    (net (code "25") (name "Net-(LED2-A)") (class "Default")
      (node (ref "LED2") (pin "2") (pinfunction "A_2") (pintype "bidirectional"))
      (node (ref "R5") (pin "2") (pinfunction "2_2") (pintype "passive"))
    )
    (net (code "26") (name "Net-(Q1-D)") (class "Default")
      (node (ref "C16") (pin "2") (pinfunction "2_2") (pintype "passive"))
      (node (ref "C19") (pin "2") (pinfunction "2_2") (pintype "passive"))
      (node (ref "Q1") (pin "1") (pinfunction "D_1") (pintype "passive"))
      (node (ref "U6") (pin "3") (pinfunction "GND_3") (pintype "bidirectional"))
    )
    (net (code "27") (name "Net-(Q1-G)") (class "Default")
      (node (ref "Q1") (pin "3") (pinfunction "G_3") (pintype "passive"))
      (node (ref "R18") (pin "2") (pinfunction "2_2") (pintype "passive"))
      (node (ref "R19") (pin "1") (pinfunction "1_1") (pintype "passive"))
    )
    (net (code "28") (name "Net-(Q3-G)") (class "Default")
      (node (ref "Q3") (pin "3") (pinfunction "G_3") (pintype "passive"))
      (node (ref "R20") (pin "1") (pinfunction "1_1") (pintype "passive"))
    )
    (net (code "29") (name "Net-(Q3-S)") (class "Default")
      (node (ref "F1") (pin "2") (pinfunction "2_2") (pintype "bidirectional"))
      (node (ref "Q3") (pin "2") (pinfunction "S_2") (pintype "passive"))
    )
    (net (code "30") (name "Net-(S1-NO)") (class "Default")
      (node (ref "C7") (pin "1") (pinfunction "1_1") (pintype "passive"))
      (node (ref "R3") (pin "2") (pinfunction "2_2") (pintype "passive"))
      (node (ref "S1") (pin "2") (pinfunction "NO_2") (pintype "bidirectional"))
      (node (ref "U2") (pin "26") (pinfunction "PF6(~{RST})_26") (pintype "bidirectional"))
    )
    (net (code "31") (name "Net-(U1-X1)") (class "Default")
      (node (ref "C6") (pin "1") (pinfunction "1_1") (pintype "passive"))
      (node (ref "U1") (pin "1") (pinfunction "X1_1") (pintype "input"))
      (node (ref "Y1") (pin "2") (pinfunction "2_2") (pintype "passive"))
    )
    (net (code "32") (name "Net-(U1-X2)") (class "Default")
      (node (ref "C5") (pin "1") (pinfunction "1_1") (pintype "passive"))
      (node (ref "U1") (pin "2") (pinfunction "X2_2") (pintype "input"))
      (node (ref "Y1") (pin "1") (pinfunction "1_1") (pintype "passive"))
    )
    (net (code "33") (name "Net-(U2-PF0(TOSC1))") (class "Default")
      (node (ref "C8") (pin "1") (pinfunction "1_1") (pintype "passive"))
      (node (ref "U2") (pin "20") (pinfunction "PF0(TOSC1)_20") (pintype "bidirectional"))
      (node (ref "Y2") (pin "1") (pinfunction "1_1") (pintype "passive"))
    )
    (net (code "34") (name "Net-(U2-PF1(TOSC2))") (class "Default")
      (node (ref "C9") (pin "1") (pinfunction "1_1") (pintype "passive"))
      (node (ref "U2") (pin "21") (pinfunction "PF1(TOSC2)_21") (pintype "bidirectional"))
      (node (ref "Y2") (pin "2") (pinfunction "2_2") (pintype "passive"))
    )
    (net (code "35") (name "Net-(U4A-+IN)") (class "Default")
      (node (ref "R7") (pin "2") (pinfunction "2_2") (pintype "passive"))
      (node (ref "R8") (pin "1") (pinfunction "1_1") (pintype "passive"))
      (node (ref "U4") (pin "3") (pinfunction "+IN_3") (pintype "input"))
    )
    (net (code "36") (name "Net-(U4B-+IN)") (class "Default")
      (node (ref "C19") (pin "1") (pinfunction "1_1") (pintype "passive"))
      (node (ref "R17") (pin "2") (pinfunction "2_2") (pintype "passive"))
      (node (ref "U4") (pin "5") (pinfunction "+IN_5") (pintype "input"))
    )
    (net (code "37") (name "Net-(U5-REF)") (class "Default")
      (node (ref "C15") (pin "1") (pinfunction "1_1") (pintype "passive"))
      (node (ref "R10") (pin "1") (pinfunction "1_1") (pintype "passive"))
      (node (ref "R9") (pin "2") (pinfunction "2_2") (pintype "passive"))
      (node (ref "U5") (pin "11") (pinfunction "REF_11") (pintype "bidirectional"))
    )
    (net (code "38") (name "Net-(U5-SENSEA)") (class "Default")
      (node (ref "R11") (pin "1") (pinfunction "1_1") (pintype "passive"))
      (node (ref "R12") (pin "1") (pinfunction "1_1") (pintype "passive"))
      (node (ref "U5") (pin "4") (pinfunction "SENSEA_4") (pintype "bidirectional"))
    )
    (net (code "39") (name "Net-(U5-TOFF)") (class "Default")
      (node (ref "R14") (pin "1") (pinfunction "1_1") (pintype "passive"))
      (node (ref "R15") (pin "1") (pinfunction "1_1") (pintype "passive"))
      (node (ref "U5") (pin "12") (pinfunction "TOFF_12") (pintype "bidirectional"))
    )
    (net (code "40") (name "RTCC_ALARM_INT") (class "Default")
      (node (ref "U1") (pin "7") (pinfunction "MFP_7") (pintype "bidirectional"))
      (node (ref "U2") (pin "32") (pinfunction "PA2_32") (pintype "bidirectional"))
    )
    (net (code "41") (name "SPI0_MISO") (class "Default")
      (node (ref "U2") (pin "3") (pinfunction "PA5_3") (pintype "bidirectional"))
      (node (ref "U3") (pin "2") (pinfunction "SO/SIO1_2") (pintype "bidirectional"))
    )
    (net (code "42") (name "SPI0_MOSI") (class "Default")
      (node (ref "U2") (pin "2") (pinfunction "PA4_2") (pintype "bidirectional"))
      (node (ref "U3") (pin "5") (pinfunction "SI/SIO0_5") (pintype "bidirectional"))
    )
    (net (code "43") (name "SPI0_SCK") (class "Default")
      (node (ref "U2") (pin "4") (pinfunction "PA6_4") (pintype "bidirectional"))
      (node (ref "U3") (pin "6") (pinfunction "SCLK_6") (pintype "input"))
    )
    (net (code "44") (name "UART_RX") (class "Default")
      (node (ref "J1") (pin "3") (pinfunction "3_3") (pintype "passive"))
      (node (ref "U2") (pin "31") (pinfunction "PA1_31") (pintype "bidirectional"))
    )
    (net (code "45") (name "UART_TX") (class "Default")
      (node (ref "J1") (pin "2") (pinfunction "2_2") (pintype "passive"))
      (node (ref "U2") (pin "30") (pinfunction "PA0(EXTCLK)_30") (pintype "bidirectional"))
    )
    (net (code "46") (name "UPDI") (class "Default")
      (node (ref "J1") (pin "5") (pinfunction "5_5") (pintype "passive"))
      (node (ref "U2") (pin "27") (pinfunction "UPDI_27") (pintype "bidirectional"))
    )
    (net (code "47") (name "V_BAT") (class "Default")
      (node (ref "C12") (pin "1") (pinfunction "+_1") (pintype "bidirectional"))
      (node (ref "C13") (pin "1") (pinfunction "1_1") (pintype "passive"))
      (node (ref "C20") (pin "1") (pinfunction "1_1") (pintype "passive"))
      (node (ref "J1") (pin "1") (pinfunction "1_1") (pintype "passive"))
      (node (ref "Q3") (pin "1") (pinfunction "D_1") (pintype "passive"))
      (node (ref "R7") (pin "1") (pinfunction "1_1") (pintype "passive"))
      (node (ref "U5") (pin "6") (pinfunction "VS_6") (pintype "bidirectional"))
      (node (ref "U7") (pin "1") (pinfunction "VIN_1") (pintype "power_in"))
      (node (ref "U7") (pin "3") (pinfunction "EN_3") (pintype "input"))
    )
    (net (code "48") (name "unconnected-(U2-PA7-Pad5)") (class "Default")
      (node (ref "U2") (pin "5") (pinfunction "PA7_5") (pintype "bidirectional"))
    )
    (net (code "49") (name "unconnected-(U2-PC0-Pad6)") (class "Default")
      (node (ref "U2") (pin "6") (pinfunction "PC0_6") (pintype "bidirectional"))
    )
    (net (code "50") (name "unconnected-(U3-SIO2{slash}~{WP}-Pad3)") (class "Default")
      (node (ref "U3") (pin "3") (pinfunction "SIO2/~{WP}_3") (pintype "bidirectional"))
    )
    (net (code "51") (name "unconnected-(U3-SIO3{slash}~{HOLD}-Pad7)") (class "Default")
      (node (ref "U3") (pin "7") (pinfunction "SIO3/~{HOLD}_7") (pintype "bidirectional"))
    )
    (net (code "52") (name "unconnected-(U5-OUTB1-Pad10)") (class "Default")
      (node (ref "U5") (pin "10") (pinfunction "OUTB1_10") (pintype "bidirectional"))
    )
    (net (code "53") (name "unconnected-(U5-OUTB2-Pad8)") (class "Default")
      (node (ref "U5") (pin "8") (pinfunction "OUTB2_8") (pintype "bidirectional"))
    )
    (net (code "54") (name "unconnected-(U5-SENSEB-Pad9)") (class "Default")
      (node (ref "U5") (pin "9") (pinfunction "SENSEB_9") (pintype "bidirectional"))
    )
    (net (code "55") (name "~{CS_FLASH}") (class "Default")
      (node (ref "U2") (pin "1") (pinfunction "PA3_1") (pintype "bidirectional"))
      (node (ref "U3") (pin "1") (pinfunction "~{CS}_1") (pintype "input"))
    )
    (net (code "56") (name "~{GRN_LED_EN}") (class "Default")
      (node (ref "LED1") (pin "1") (pinfunction "K_1") (pintype "bidirectional"))
      (node (ref "U2") (pin "11") (pinfunction "PD1_11") (pintype "bidirectional"))
    )
    (net (code "57") (name "~{MTR_FAULT}") (class "Default")
      (node (ref "J3") (pin "4") (pinfunction "4_4") (pintype "passive"))
      (node (ref "U2") (pin "15") (pinfunction "PD5_15") (pintype "bidirectional"))
    )
    (net (code "58") (name "~{MTR_STBY}") (class "Default")
      (node (ref "C17") (pin "1") (pinfunction "1_1") (pintype "passive"))
      (node (ref "R13") (pin "2") (pinfunction "2_2") (pintype "passive"))
      (node (ref "U2") (pin "17") (pinfunction "PD7_17") (pintype "bidirectional"))
      (node (ref "U5") (pin "14") (pinfunction "~{STBY/RESET}_14") (pintype "bidirectional"))
    )
    (net (code "59") (name "~{RED_LED_EN}") (class "Default")
      (node (ref "LED2") (pin "1") (pinfunction "K_1") (pintype "bidirectional"))
      (node (ref "U2") (pin "10") (pinfunction "PD0_10") (pintype "bidirectional"))
    )
  )
)
